# internship_emu_-_Copy.net
KiCad netlist of a schematic drawn in EAGLE
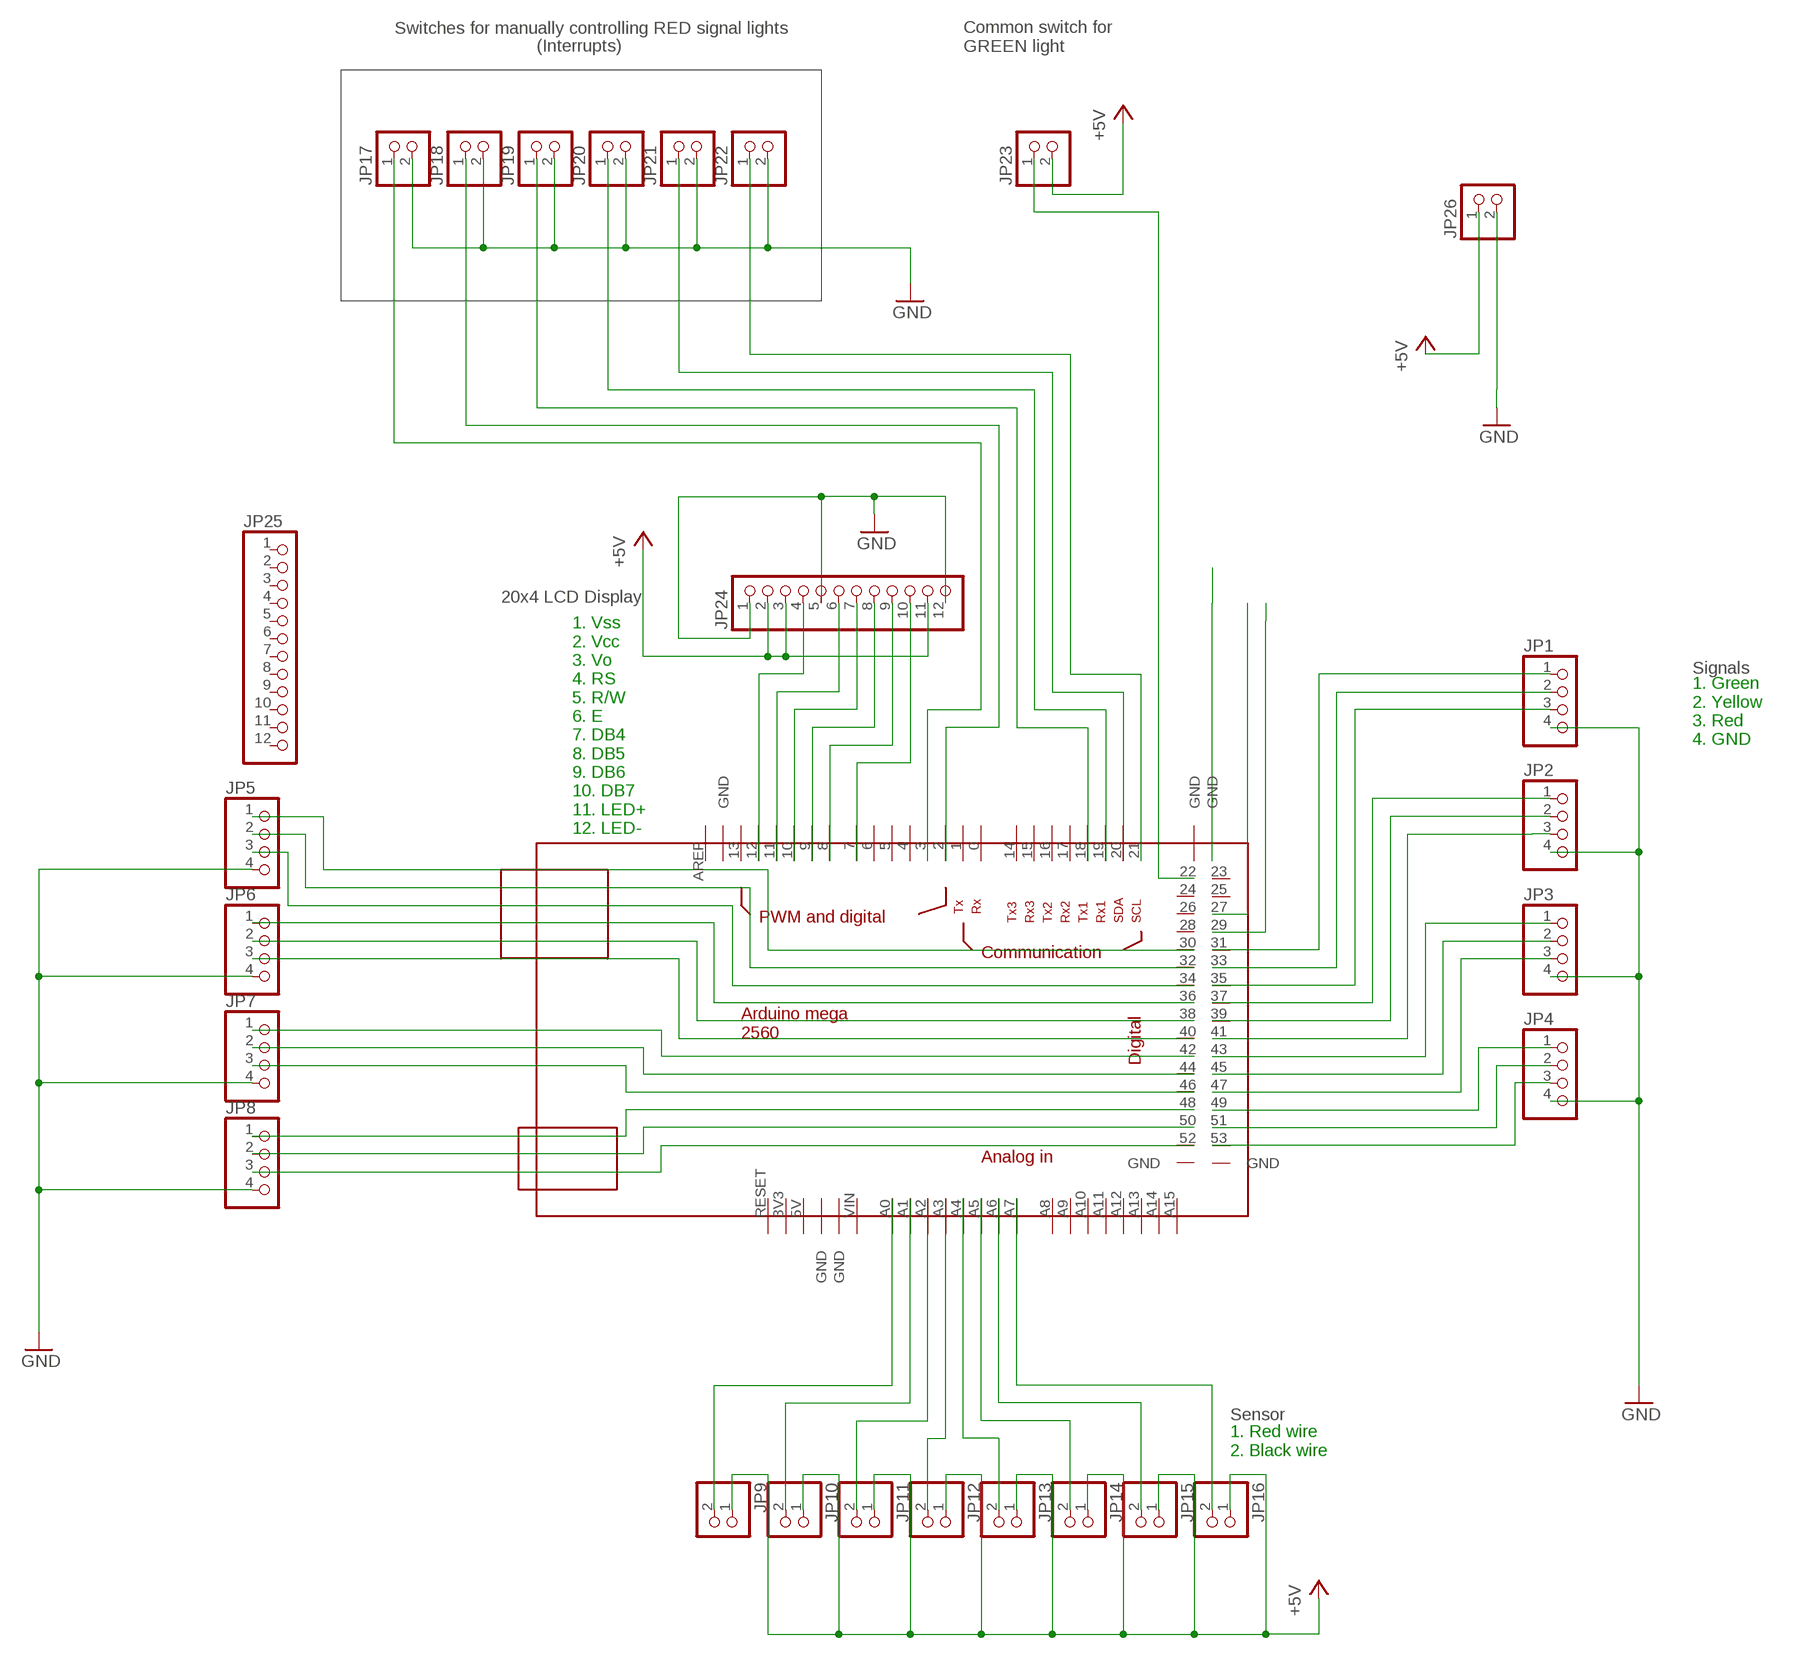
[diagram p0: schematic, sheet 1]

(export (version "E")
  (design (tool "Eeschema 10.0.6"))
  (components
    (comp (ref "JP1")
      (value "PINHD-1X4")
      (footprint "eagle-import:1X04")
      (libsource (lib "eagle-import") (part "PINHD-1X4"))
    )
    (comp (ref "JP2")
      (value "PINHD-1X4")
      (footprint "eagle-import:1X04")
      (libsource (lib "eagle-import") (part "PINHD-1X4"))
    )
    (comp (ref "JP3")
      (value "PINHD-1X4")
      (footprint "eagle-import:1X04")
      (libsource (lib "eagle-import") (part "PINHD-1X4"))
    )
    (comp (ref "JP4")
      (value "PINHD-1X4")
      (footprint "eagle-import:1X04")
      (libsource (lib "eagle-import") (part "PINHD-1X4"))
    )
    (comp (ref "JP5")
      (value "PINHD-1X4")
      (footprint "eagle-import:1X04")
      (libsource (lib "eagle-import") (part "PINHD-1X4"))
    )
    (comp (ref "JP6")
      (value "PINHD-1X4")
      (footprint "eagle-import:1X04")
      (libsource (lib "eagle-import") (part "PINHD-1X4"))
    )
    (comp (ref "JP7")
      (value "PINHD-1X4")
      (footprint "eagle-import:1X04")
      (libsource (lib "eagle-import") (part "PINHD-1X4"))
    )
    (comp (ref "JP8")
      (value "PINHD-1X4")
      (footprint "eagle-import:1X04")
      (libsource (lib "eagle-import") (part "PINHD-1X4"))
    )
    (comp (ref "JP9")
      (value "PINHD-1X2")
      (footprint "eagle-import:1X02")
      (libsource (lib "eagle-import") (part "PINHD-1X2"))
    )
    (comp (ref "JP10")
      (value "PINHD-1X2")
      (footprint "eagle-import:1X02")
      (libsource (lib "eagle-import") (part "PINHD-1X2"))
    )
    (comp (ref "JP11")
      (value "PINHD-1X2")
      (footprint "eagle-import:1X02")
      (libsource (lib "eagle-import") (part "PINHD-1X2"))
    )
    (comp (ref "JP12")
      (value "PINHD-1X2")
      (footprint "eagle-import:1X02")
      (libsource (lib "eagle-import") (part "PINHD-1X2"))
    )
    (comp (ref "JP13")
      (value "PINHD-1X2")
      (footprint "eagle-import:1X02")
      (libsource (lib "eagle-import") (part "PINHD-1X2"))
    )
    (comp (ref "JP14")
      (value "PINHD-1X2")
      (footprint "eagle-import:1X02")
      (libsource (lib "eagle-import") (part "PINHD-1X2"))
    )
    (comp (ref "JP15")
      (value "PINHD-1X2")
      (footprint "eagle-import:1X02")
      (libsource (lib "eagle-import") (part "PINHD-1X2"))
    )
    (comp (ref "JP16")
      (value "PINHD-1X2")
      (footprint "eagle-import:1X02")
      (libsource (lib "eagle-import") (part "PINHD-1X2"))
    )
    (comp (ref "JP17")
      (value "PINHD-1X2")
      (footprint "eagle-import:1X02")
      (libsource (lib "eagle-import") (part "PINHD-1X2"))
    )
    (comp (ref "JP18")
      (value "PINHD-1X2")
      (footprint "eagle-import:1X02")
      (libsource (lib "eagle-import") (part "PINHD-1X2"))
    )
    (comp (ref "JP19")
      (value "PINHD-1X2")
      (footprint "eagle-import:1X02")
      (libsource (lib "eagle-import") (part "PINHD-1X2"))
    )
    (comp (ref "JP20")
      (value "PINHD-1X2")
      (footprint "eagle-import:1X02")
      (libsource (lib "eagle-import") (part "PINHD-1X2"))
    )
    (comp (ref "JP21")
      (value "PINHD-1X2")
      (footprint "eagle-import:1X02")
      (libsource (lib "eagle-import") (part "PINHD-1X2"))
    )
    (comp (ref "JP22")
      (value "PINHD-1X2")
      (footprint "eagle-import:1X02")
      (libsource (lib "eagle-import") (part "PINHD-1X2"))
    )
    (comp (ref "JP23")
      (value "PINHD-1X2")
      (footprint "eagle-import:1X02")
      (libsource (lib "eagle-import") (part "PINHD-1X2"))
    )
    (comp (ref "JP24")
      (value "PINHD-1X12")
      (footprint "eagle-import:1X12")
      (libsource (lib "eagle-import") (part "PINHD-1X12"))
    )
    (comp (ref "JP25")
      (value "PINHD-1X12")
      (footprint "eagle-import:1X12")
      (libsource (lib "eagle-import") (part "PINHD-1X12"))
    )
    (comp (ref "JP26")
      (value "PINHD-1X2")
      (footprint "eagle-import:1X02")
      (libsource (lib "eagle-import") (part "PINHD-1X2"))
    )
    (comp (ref "U$1")
      (value "MEGA_DEVICE")
      (footprint "eagle-import:MEGAOUTLINE")
      (libsource (lib "eagle-import") (part "MEGA_DEVICE"))
    )
  )
  (nets
    (net (code "1") (name "+5V") (class "Default")
      (node (ref "JP10") (pin "1") (pinfunction "1_1") (pintype "passive"))
      (node (ref "JP11") (pin "1") (pinfunction "1_1") (pintype "passive"))
      (node (ref "JP12") (pin "1") (pinfunction "1_1") (pintype "passive"))
      (node (ref "JP13") (pin "1") (pinfunction "1_1") (pintype "passive"))
      (node (ref "JP14") (pin "1") (pinfunction "1_1") (pintype "passive"))
      (node (ref "JP15") (pin "1") (pinfunction "1_1") (pintype "passive"))
      (node (ref "JP16") (pin "1") (pinfunction "1_1") (pintype "passive"))
      (node (ref "JP23") (pin "2") (pinfunction "2_2") (pintype "passive"))
      (node (ref "JP24") (pin "11") (pinfunction "11_11") (pintype "passive"))
      (node (ref "JP24") (pin "2") (pinfunction "2_2") (pintype "passive"))
      (node (ref "JP24") (pin "3") (pinfunction "3_3") (pintype "passive"))
      (node (ref "JP26") (pin "1") (pinfunction "1_1") (pintype "passive"))
      (node (ref "JP9") (pin "1") (pinfunction "1_1") (pintype "passive"))
    )
    (net (code "2") (name "GND") (class "Default")
      (node (ref "JP1") (pin "4") (pinfunction "4_4") (pintype "passive"))
      (node (ref "JP17") (pin "2") (pinfunction "2_2") (pintype "passive"))
      (node (ref "JP18") (pin "2") (pinfunction "2_2") (pintype "passive"))
      (node (ref "JP19") (pin "2") (pinfunction "2_2") (pintype "passive"))
      (node (ref "JP2") (pin "4") (pinfunction "4_4") (pintype "passive"))
      (node (ref "JP20") (pin "2") (pinfunction "2_2") (pintype "passive"))
      (node (ref "JP21") (pin "2") (pinfunction "2_2") (pintype "passive"))
      (node (ref "JP22") (pin "2") (pinfunction "2_2") (pintype "passive"))
      (node (ref "JP24") (pin "1") (pinfunction "1_1") (pintype "passive"))
      (node (ref "JP24") (pin "12") (pinfunction "12_12") (pintype "passive"))
      (node (ref "JP24") (pin "5") (pinfunction "5_5") (pintype "passive"))
      (node (ref "JP26") (pin "2") (pinfunction "2_2") (pintype "passive"))
      (node (ref "JP3") (pin "4") (pinfunction "4_4") (pintype "passive"))
      (node (ref "JP4") (pin "4") (pinfunction "4_4") (pintype "passive"))
      (node (ref "JP5") (pin "4") (pinfunction "4_4") (pintype "passive"))
      (node (ref "JP6") (pin "4") (pinfunction "4_4") (pintype "passive"))
      (node (ref "JP7") (pin "4") (pinfunction "4_4") (pintype "passive"))
      (node (ref "JP8") (pin "4") (pinfunction "4_4") (pintype "passive"))
    )
    (net (code "3") (name "Net-(JP1-Pad1)") (class "Default")
      (node (ref "JP1") (pin "1") (pinfunction "1_1") (pintype "passive"))
      (node (ref "U$1") (pin "31") (pinfunction "31_31") (pintype "bidirectional"))
    )
    (net (code "4") (name "Net-(JP1-Pad2)") (class "Default")
      (node (ref "JP1") (pin "2") (pinfunction "2_2") (pintype "passive"))
      (node (ref "U$1") (pin "33") (pinfunction "33_33") (pintype "bidirectional"))
    )
    (net (code "5") (name "Net-(JP1-Pad3)") (class "Default")
      (node (ref "JP1") (pin "3") (pinfunction "3_3") (pintype "passive"))
      (node (ref "U$1") (pin "35") (pinfunction "35_35") (pintype "bidirectional"))
    )
    (net (code "6") (name "Net-(JP2-Pad1)") (class "Default")
      (node (ref "JP2") (pin "1") (pinfunction "1_1") (pintype "passive"))
      (node (ref "U$1") (pin "37") (pinfunction "37_37") (pintype "bidirectional"))
    )
    (net (code "7") (name "Net-(JP2-Pad2)") (class "Default")
      (node (ref "JP2") (pin "2") (pinfunction "2_2") (pintype "passive"))
      (node (ref "U$1") (pin "39") (pinfunction "39_39") (pintype "bidirectional"))
    )
    (net (code "8") (name "Net-(JP2-Pad3)") (class "Default")
      (node (ref "JP2") (pin "3") (pinfunction "3_3") (pintype "passive"))
      (node (ref "U$1") (pin "41") (pinfunction "41_41") (pintype "bidirectional"))
    )
    (net (code "9") (name "Net-(JP3-Pad1)") (class "Default")
      (node (ref "JP3") (pin "1") (pinfunction "1_1") (pintype "passive"))
      (node (ref "U$1") (pin "43") (pinfunction "43_43") (pintype "bidirectional"))
    )
    (net (code "10") (name "Net-(JP3-Pad2)") (class "Default")
      (node (ref "JP3") (pin "2") (pinfunction "2_2") (pintype "passive"))
      (node (ref "U$1") (pin "45") (pinfunction "45_45") (pintype "bidirectional"))
    )
    (net (code "11") (name "Net-(JP3-Pad3)") (class "Default")
      (node (ref "JP3") (pin "3") (pinfunction "3_3") (pintype "passive"))
      (node (ref "U$1") (pin "47") (pinfunction "47_47") (pintype "bidirectional"))
    )
    (net (code "12") (name "Net-(JP4-Pad1)") (class "Default")
      (node (ref "JP4") (pin "1") (pinfunction "1_1") (pintype "passive"))
      (node (ref "U$1") (pin "49") (pinfunction "49_49") (pintype "bidirectional"))
    )
    (net (code "13") (name "Net-(JP4-Pad2)") (class "Default")
      (node (ref "JP4") (pin "2") (pinfunction "2_2") (pintype "passive"))
      (node (ref "U$1") (pin "51") (pinfunction "51_51") (pintype "bidirectional"))
    )
    (net (code "14") (name "Net-(JP4-Pad3)") (class "Default")
      (node (ref "JP4") (pin "3") (pinfunction "3_3") (pintype "passive"))
      (node (ref "U$1") (pin "53") (pinfunction "53_53") (pintype "bidirectional"))
    )
    (net (code "15") (name "Net-(JP5-Pad1)") (class "Default")
      (node (ref "JP5") (pin "1") (pinfunction "1_1") (pintype "passive"))
      (node (ref "U$1") (pin "30") (pinfunction "30_30") (pintype "bidirectional"))
    )
    (net (code "16") (name "Net-(JP5-Pad2)") (class "Default")
      (node (ref "JP5") (pin "2") (pinfunction "2_2") (pintype "passive"))
      (node (ref "U$1") (pin "32") (pinfunction "32_32") (pintype "bidirectional"))
    )
    (net (code "17") (name "Net-(JP5-Pad3)") (class "Default")
      (node (ref "JP5") (pin "3") (pinfunction "3_3") (pintype "passive"))
      (node (ref "U$1") (pin "34") (pinfunction "34_34") (pintype "bidirectional"))
    )
    (net (code "18") (name "Net-(JP6-Pad1)") (class "Default")
      (node (ref "JP6") (pin "1") (pinfunction "1_1") (pintype "passive"))
      (node (ref "U$1") (pin "36") (pinfunction "36_36") (pintype "bidirectional"))
    )
    (net (code "19") (name "Net-(JP6-Pad2)") (class "Default")
      (node (ref "JP6") (pin "2") (pinfunction "2_2") (pintype "passive"))
      (node (ref "U$1") (pin "38") (pinfunction "38_38") (pintype "bidirectional"))
    )
    (net (code "20") (name "Net-(JP6-Pad3)") (class "Default")
      (node (ref "JP6") (pin "3") (pinfunction "3_3") (pintype "passive"))
      (node (ref "U$1") (pin "40") (pinfunction "40_40") (pintype "bidirectional"))
    )
    (net (code "21") (name "Net-(JP7-Pad1)") (class "Default")
      (node (ref "JP7") (pin "1") (pinfunction "1_1") (pintype "passive"))
      (node (ref "U$1") (pin "42") (pinfunction "42_42") (pintype "bidirectional"))
    )
    (net (code "22") (name "Net-(JP7-Pad2)") (class "Default")
      (node (ref "JP7") (pin "2") (pinfunction "2_2") (pintype "passive"))
      (node (ref "U$1") (pin "44") (pinfunction "44_44") (pintype "bidirectional"))
    )
    (net (code "23") (name "Net-(JP7-Pad3)") (class "Default")
      (node (ref "JP7") (pin "3") (pinfunction "3_3") (pintype "passive"))
      (node (ref "U$1") (pin "46") (pinfunction "46_46") (pintype "bidirectional"))
    )
    (net (code "24") (name "Net-(JP8-Pad1)") (class "Default")
      (node (ref "JP8") (pin "1") (pinfunction "1_1") (pintype "passive"))
      (node (ref "U$1") (pin "48") (pinfunction "48_48") (pintype "bidirectional"))
    )
    (net (code "25") (name "Net-(JP8-Pad2)") (class "Default")
      (node (ref "JP8") (pin "2") (pinfunction "2_2") (pintype "passive"))
      (node (ref "U$1") (pin "50") (pinfunction "50_50") (pintype "bidirectional"))
    )
    (net (code "26") (name "Net-(JP8-Pad3)") (class "Default")
      (node (ref "JP8") (pin "3") (pinfunction "3_3") (pintype "passive"))
      (node (ref "U$1") (pin "52") (pinfunction "52_52") (pintype "bidirectional"))
    )
    (net (code "27") (name "Net-(JP9-Pad2)") (class "Default")
      (node (ref "JP9") (pin "2") (pinfunction "2_2") (pintype "passive"))
      (node (ref "U$1") (pin "A0") (pinfunction "A0_A0") (pintype "bidirectional"))
    )
    (net (code "28") (name "Net-(JP10-Pad2)") (class "Default")
      (node (ref "JP10") (pin "2") (pinfunction "2_2") (pintype "passive"))
      (node (ref "U$1") (pin "A1") (pinfunction "A1_A1") (pintype "bidirectional"))
    )
    (net (code "29") (name "Net-(JP11-Pad2)") (class "Default")
      (node (ref "JP11") (pin "2") (pinfunction "2_2") (pintype "passive"))
      (node (ref "U$1") (pin "A2") (pinfunction "A2_A2") (pintype "bidirectional"))
    )
    (net (code "30") (name "Net-(JP12-Pad2)") (class "Default")
      (node (ref "JP12") (pin "2") (pinfunction "2_2") (pintype "passive"))
      (node (ref "U$1") (pin "A3") (pinfunction "A3_A3") (pintype "bidirectional"))
    )
    (net (code "31") (name "Net-(JP13-Pad2)") (class "Default")
      (node (ref "JP13") (pin "2") (pinfunction "2_2") (pintype "passive"))
      (node (ref "U$1") (pin "A4") (pinfunction "A4_A4") (pintype "bidirectional"))
    )
    (net (code "32") (name "Net-(JP14-Pad2)") (class "Default")
      (node (ref "JP14") (pin "2") (pinfunction "2_2") (pintype "passive"))
      (node (ref "U$1") (pin "A5") (pinfunction "A5_A5") (pintype "bidirectional"))
    )
    (net (code "33") (name "Net-(JP15-Pad2)") (class "Default")
      (node (ref "JP15") (pin "2") (pinfunction "2_2") (pintype "passive"))
      (node (ref "U$1") (pin "A6") (pinfunction "A6_A6") (pintype "bidirectional"))
    )
    (net (code "34") (name "Net-(JP16-Pad2)") (class "Default")
      (node (ref "JP16") (pin "2") (pinfunction "2_2") (pintype "passive"))
      (node (ref "U$1") (pin "A7") (pinfunction "A7_A7") (pintype "bidirectional"))
    )
    (net (code "35") (name "Net-(JP17-Pad1)") (class "Default")
      (node (ref "JP17") (pin "1") (pinfunction "1_1") (pintype "passive"))
      (node (ref "U$1") (pin "3") (pinfunction "3_3") (pintype "bidirectional"))
    )
    (net (code "36") (name "Net-(JP18-Pad1)") (class "Default")
      (node (ref "JP18") (pin "1") (pinfunction "1_1") (pintype "passive"))
      (node (ref "U$1") (pin "2") (pinfunction "2_2") (pintype "bidirectional"))
    )
    (net (code "37") (name "Net-(JP19-Pad1)") (class "Default")
      (node (ref "JP19") (pin "1") (pinfunction "1_1") (pintype "passive"))
      (node (ref "U$1") (pin "18") (pinfunction "18_18") (pintype "bidirectional"))
    )
    (net (code "38") (name "Net-(JP20-Pad1)") (class "Default")
      (node (ref "JP20") (pin "1") (pinfunction "1_1") (pintype "passive"))
      (node (ref "U$1") (pin "19") (pinfunction "19_19") (pintype "bidirectional"))
    )
    (net (code "39") (name "Net-(JP21-Pad1)") (class "Default")
      (node (ref "JP21") (pin "1") (pinfunction "1_1") (pintype "passive"))
      (node (ref "U$1") (pin "20") (pinfunction "20_20") (pintype "bidirectional"))
    )
    (net (code "40") (name "Net-(JP22-Pad1)") (class "Default")
      (node (ref "JP22") (pin "1") (pinfunction "1_1") (pintype "passive"))
      (node (ref "U$1") (pin "21") (pinfunction "21_21") (pintype "bidirectional"))
    )
    (net (code "41") (name "Net-(JP23-Pad1)") (class "Default")
      (node (ref "JP23") (pin "1") (pinfunction "1_1") (pintype "passive"))
      (node (ref "U$1") (pin "22") (pinfunction "22_22") (pintype "bidirectional"))
    )
    (net (code "42") (name "Net-(JP24-Pad4)") (class "Default")
      (node (ref "JP24") (pin "4") (pinfunction "4_4") (pintype "passive"))
      (node (ref "U$1") (pin "12") (pinfunction "12_12") (pintype "bidirectional"))
    )
    (net (code "43") (name "Net-(JP24-Pad6)") (class "Default")
      (node (ref "JP24") (pin "6") (pinfunction "6_6") (pintype "passive"))
      (node (ref "U$1") (pin "11") (pinfunction "11_11") (pintype "bidirectional"))
    )
    (net (code "44") (name "Net-(JP24-Pad7)") (class "Default")
      (node (ref "JP24") (pin "7") (pinfunction "7_7") (pintype "passive"))
      (node (ref "U$1") (pin "10") (pinfunction "10_10") (pintype "bidirectional"))
    )
    (net (code "45") (name "Net-(JP24-Pad8)") (class "Default")
      (node (ref "JP24") (pin "8") (pinfunction "8_8") (pintype "passive"))
      (node (ref "U$1") (pin "9") (pinfunction "9_9") (pintype "bidirectional"))
    )
    (net (code "46") (name "Net-(JP24-Pad9)") (class "Default")
      (node (ref "JP24") (pin "9") (pinfunction "9_9") (pintype "passive"))
      (node (ref "U$1") (pin "8") (pinfunction "8_8") (pintype "bidirectional"))
    )
    (net (code "47") (name "Net-(JP24-Pad10)") (class "Default")
      (node (ref "JP24") (pin "10") (pinfunction "10_10") (pintype "passive"))
      (node (ref "U$1") (pin "7") (pinfunction "7_7") (pintype "bidirectional"))
    )
    (net (code "48") (name "unconnected-(JP25-Pad1)") (class "Default")
      (node (ref "JP25") (pin "1") (pinfunction "1_1") (pintype "passive"))
    )
    (net (code "49") (name "unconnected-(JP25-Pad2)") (class "Default")
      (node (ref "JP25") (pin "2") (pinfunction "2_2") (pintype "passive"))
    )
    (net (code "50") (name "unconnected-(JP25-Pad3)") (class "Default")
      (node (ref "JP25") (pin "3") (pinfunction "3_3") (pintype "passive"))
    )
    (net (code "51") (name "unconnected-(JP25-Pad4)") (class "Default")
      (node (ref "JP25") (pin "4") (pinfunction "4_4") (pintype "passive"))
    )
    (net (code "52") (name "unconnected-(JP25-Pad5)") (class "Default")
      (node (ref "JP25") (pin "5") (pinfunction "5_5") (pintype "passive"))
    )
    (net (code "53") (name "unconnected-(JP25-Pad6)") (class "Default")
      (node (ref "JP25") (pin "6") (pinfunction "6_6") (pintype "passive"))
    )
    (net (code "54") (name "unconnected-(JP25-Pad7)") (class "Default")
      (node (ref "JP25") (pin "7") (pinfunction "7_7") (pintype "passive"))
    )
    (net (code "55") (name "unconnected-(JP25-Pad8)") (class "Default")
      (node (ref "JP25") (pin "8") (pinfunction "8_8") (pintype "passive"))
    )
    (net (code "56") (name "unconnected-(JP25-Pad9)") (class "Default")
      (node (ref "JP25") (pin "9") (pinfunction "9_9") (pintype "passive"))
    )
    (net (code "57") (name "unconnected-(JP25-Pad10)") (class "Default")
      (node (ref "JP25") (pin "10") (pinfunction "10_10") (pintype "passive"))
    )
    (net (code "58") (name "unconnected-(JP25-Pad11)") (class "Default")
      (node (ref "JP25") (pin "11") (pinfunction "11_11") (pintype "passive"))
    )
    (net (code "59") (name "unconnected-(JP25-Pad12)") (class "Default")
      (node (ref "JP25") (pin "12") (pinfunction "12_12") (pintype "passive"))
    )
    (net (code "60") (name "unconnected-(U$1-GND-PadGND@1)") (class "Default")
      (node (ref "U$1") (pin "GND@1") (pinfunction "GND_GND@1") (pintype "bidirectional"))
    )
    (net (code "61") (name "unconnected-(U$1-GND-PadGND@2)") (class "Default")
      (node (ref "U$1") (pin "GND@2") (pinfunction "GND_GND@2") (pintype "bidirectional"))
    )
    (net (code "62") (name "unconnected-(U$1-GND-PadGND@3)") (class "Default")
      (node (ref "U$1") (pin "GND@3") (pinfunction "GND_GND@3") (pintype "bidirectional"))
    )
    (net (code "63") (name "unconnected-(U$1-GND-PadGND@4)") (class "Default")
      (node (ref "U$1") (pin "GND@4") (pinfunction "GND_GND@4") (pintype "bidirectional"))
    )
    (net (code "64") (name "unconnected-(U$1-GND-PadGND@5)") (class "Default")
      (node (ref "U$1") (pin "GND@5") (pinfunction "GND_GND@5") (pintype "bidirectional"))
    )
    (net (code "65") (name "unconnected-(U$1-GND-PadGND@6)") (class "Default")
      (node (ref "U$1") (pin "GND@6") (pinfunction "GND_GND@6") (pintype "bidirectional"))
    )
    (net (code "66") (name "unconnected-(U$1-GND-PadGND@7)") (class "Default")
      (node (ref "U$1") (pin "GND@7") (pinfunction "GND_GND@7") (pintype "bidirectional"))
    )
    (net (code "67") (name "unconnected-(U$1-Pad0)") (class "Default")
      (node (ref "U$1") (pin "0") (pinfunction "0_0") (pintype "bidirectional"))
    )
    (net (code "68") (name "unconnected-(U$1-Pad1)") (class "Default")
      (node (ref "U$1") (pin "1") (pinfunction "1_1") (pintype "bidirectional"))
    )
    (net (code "69") (name "unconnected-(U$1-Pad3V3)") (class "Default")
      (node (ref "U$1") (pin "3V3") (pinfunction "3V3_3V3") (pintype "bidirectional"))
    )
    (net (code "70") (name "unconnected-(U$1-Pad4)") (class "Default")
      (node (ref "U$1") (pin "4") (pinfunction "4_4") (pintype "bidirectional"))
    )
    (net (code "71") (name "unconnected-(U$1-Pad5)") (class "Default")
      (node (ref "U$1") (pin "5") (pinfunction "5_5") (pintype "bidirectional"))
    )
    (net (code "72") (name "unconnected-(U$1-Pad5V)") (class "Default")
      (node (ref "U$1") (pin "5V") (pinfunction "5V_5V") (pintype "bidirectional"))
    )
    (net (code "73") (name "unconnected-(U$1-Pad6)") (class "Default")
      (node (ref "U$1") (pin "6") (pinfunction "6_6") (pintype "bidirectional"))
    )
    (net (code "74") (name "unconnected-(U$1-Pad13)") (class "Default")
      (node (ref "U$1") (pin "13") (pinfunction "13_13") (pintype "bidirectional"))
    )
    (net (code "75") (name "unconnected-(U$1-Pad14)") (class "Default")
      (node (ref "U$1") (pin "14") (pinfunction "14_14") (pintype "bidirectional"))
    )
    (net (code "76") (name "unconnected-(U$1-Pad15)") (class "Default")
      (node (ref "U$1") (pin "15") (pinfunction "15_15") (pintype "bidirectional"))
    )
    (net (code "77") (name "unconnected-(U$1-Pad16)") (class "Default")
      (node (ref "U$1") (pin "16") (pinfunction "16_16") (pintype "bidirectional"))
    )
    (net (code "78") (name "unconnected-(U$1-Pad17)") (class "Default")
      (node (ref "U$1") (pin "17") (pinfunction "17_17") (pintype "bidirectional"))
    )
    (net (code "79") (name "unconnected-(U$1-Pad23)") (class "Default")
      (node (ref "U$1") (pin "23") (pinfunction "23_23") (pintype "bidirectional"))
    )
    (net (code "80") (name "unconnected-(U$1-Pad24)") (class "Default")
      (node (ref "U$1") (pin "24") (pinfunction "24_24") (pintype "bidirectional"))
    )
    (net (code "81") (name "unconnected-(U$1-Pad25)") (class "Default")
      (node (ref "U$1") (pin "25") (pinfunction "25_25") (pintype "bidirectional"))
    )
    (net (code "82") (name "unconnected-(U$1-Pad26)") (class "Default")
      (node (ref "U$1") (pin "26") (pinfunction "26_26") (pintype "bidirectional"))
    )
    (net (code "83") (name "unconnected-(U$1-Pad27)") (class "Default")
      (node (ref "U$1") (pin "27") (pinfunction "27_27") (pintype "bidirectional"))
    )
    (net (code "84") (name "unconnected-(U$1-Pad28)") (class "Default")
      (node (ref "U$1") (pin "28") (pinfunction "28_28") (pintype "bidirectional"))
    )
    (net (code "85") (name "unconnected-(U$1-Pad29)") (class "Default")
      (node (ref "U$1") (pin "29") (pinfunction "29_29") (pintype "bidirectional"))
    )
    (net (code "86") (name "unconnected-(U$1-PadA8)") (class "Default")
      (node (ref "U$1") (pin "A8") (pinfunction "A8_A8") (pintype "bidirectional"))
    )
    (net (code "87") (name "unconnected-(U$1-PadA9)") (class "Default")
      (node (ref "U$1") (pin "A9") (pinfunction "A9_A9") (pintype "bidirectional"))
    )
    (net (code "88") (name "unconnected-(U$1-PadA10)") (class "Default")
      (node (ref "U$1") (pin "A10") (pinfunction "A10_A10") (pintype "bidirectional"))
    )
    (net (code "89") (name "unconnected-(U$1-PadA11)") (class "Default")
      (node (ref "U$1") (pin "A11") (pinfunction "A11_A11") (pintype "bidirectional"))
    )
    (net (code "90") (name "unconnected-(U$1-PadA12)") (class "Default")
      (node (ref "U$1") (pin "A12") (pinfunction "A12_A12") (pintype "bidirectional"))
    )
    (net (code "91") (name "unconnected-(U$1-PadA13)") (class "Default")
      (node (ref "U$1") (pin "A13") (pinfunction "A13_A13") (pintype "bidirectional"))
    )
    (net (code "92") (name "unconnected-(U$1-PadA14)") (class "Default")
      (node (ref "U$1") (pin "A14") (pinfunction "A14_A14") (pintype "bidirectional"))
    )
    (net (code "93") (name "unconnected-(U$1-PadA15)") (class "Default")
      (node (ref "U$1") (pin "A15") (pinfunction "A15_A15") (pintype "bidirectional"))
    )
    (net (code "94") (name "unconnected-(U$1-PadAREF)") (class "Default")
      (node (ref "U$1") (pin "AREF") (pinfunction "AREF_AREF") (pintype "bidirectional"))
    )
    (net (code "95") (name "unconnected-(U$1-PadRESET)") (class "Default")
      (node (ref "U$1") (pin "RESET") (pinfunction "RESET_RESET") (pintype "bidirectional"))
    )
    (net (code "96") (name "unconnected-(U$1-PadVIN)") (class "Default")
      (node (ref "U$1") (pin "VIN") (pinfunction "VIN_VIN") (pintype "bidirectional"))
    )
  )
)
